# MK12_IO_Shield.net
KiCad netlist of a schematic drawn in EAGLE
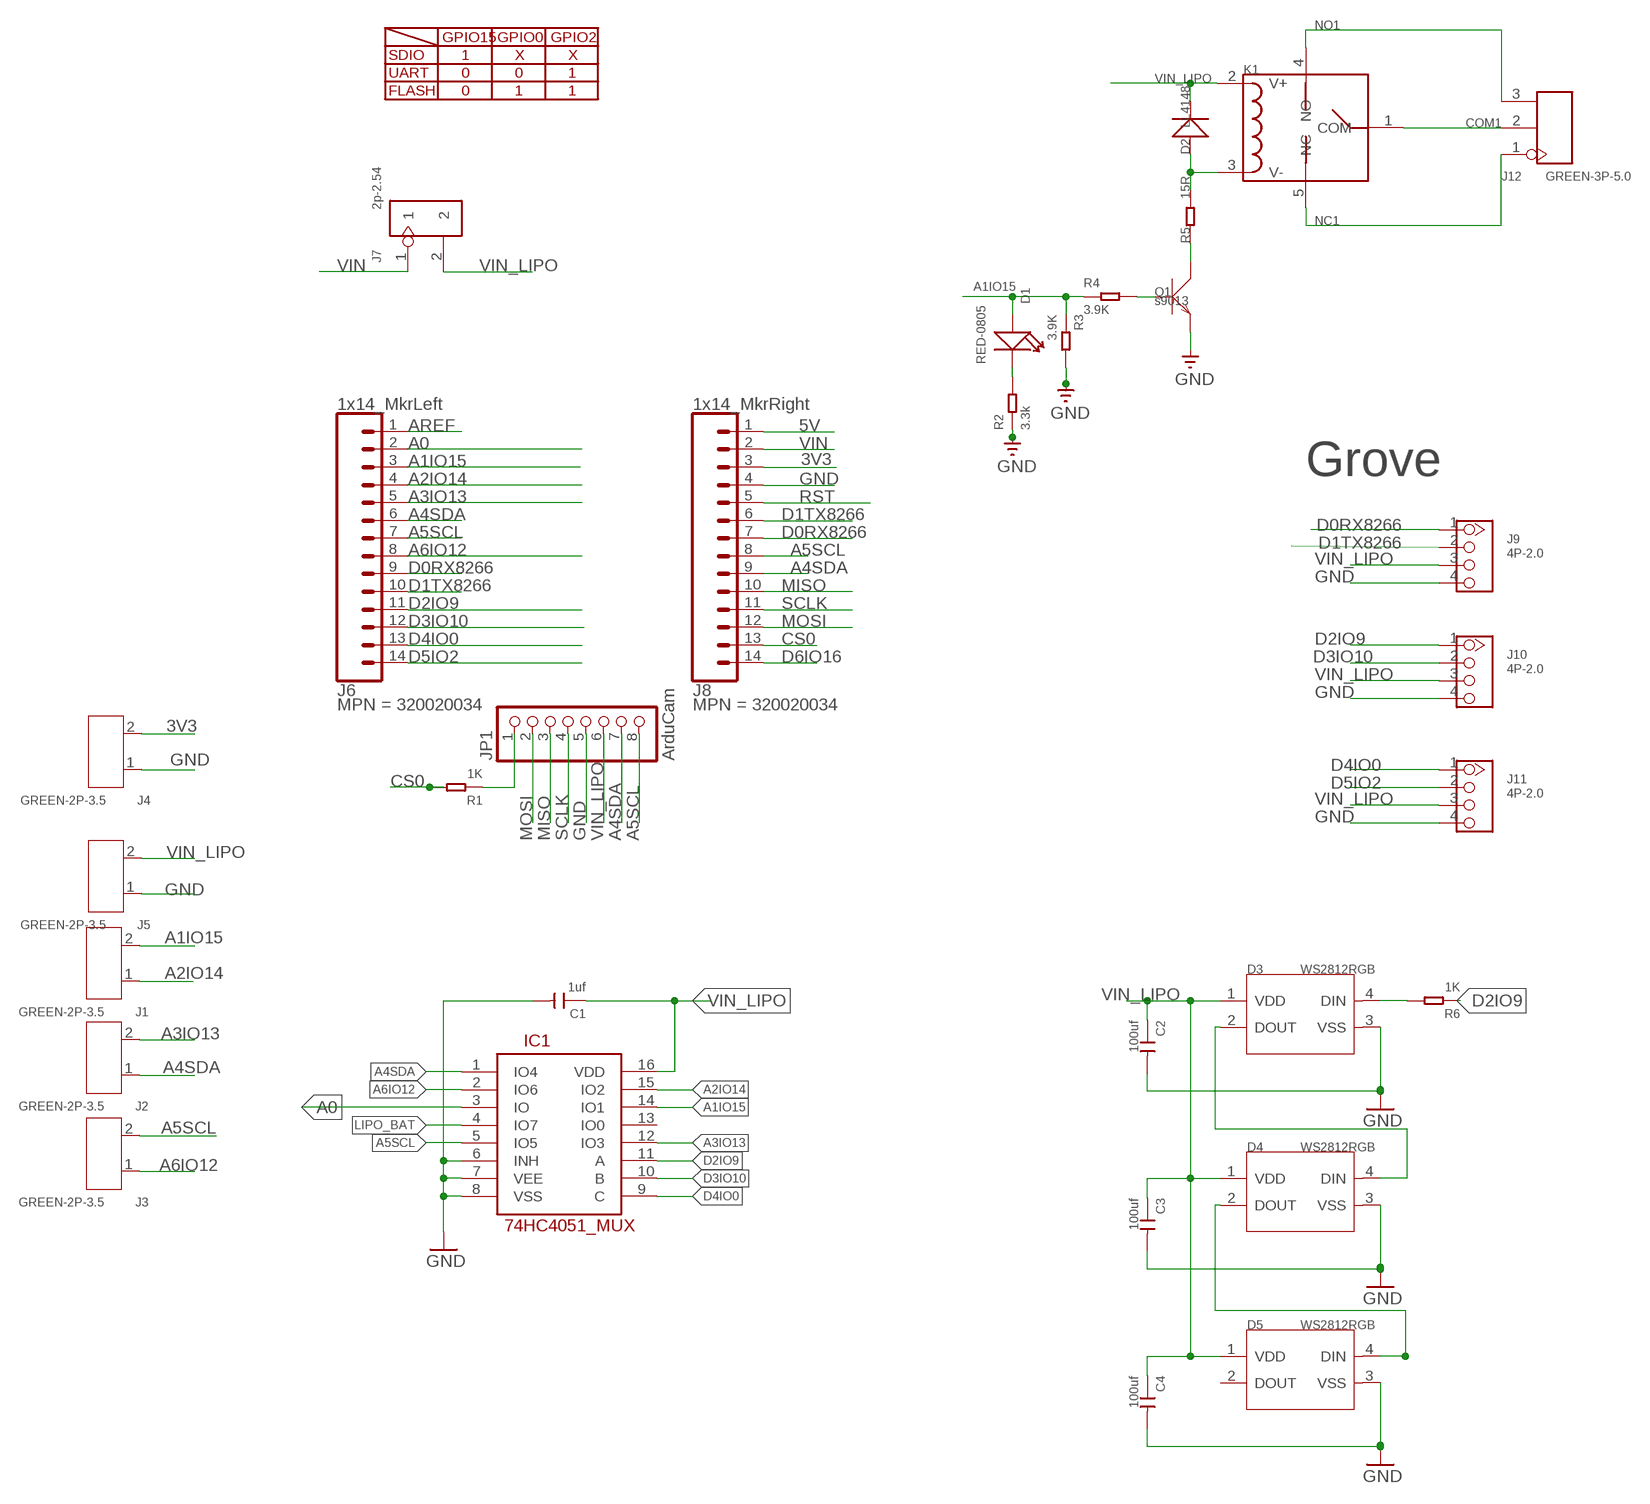
[diagram p0: schematic, sheet 1]

(export (version "E")
  (design (tool "Eeschema 10.0.6"))
  (components
    (comp (ref "C1")
      (value "1uf")
      (footprint "eagle-import:C0603")
      (fields (field (name "MPN") "CC0603KRX7R8BB105"))
      (libsource (lib "eagle-import") (part "CERAMIC-1UF-25V-10%-X7R(0603)"))
    )
    (comp (ref "C2")
      (value "100uf")
      (footprint "eagle-import:C1206")
      (fields (field (name "MPN") "GRM31CR60J107ME39L"))
      (libsource (lib "eagle-import") (part "CERAMIC-100UF-6.3V-20%-X5R(1206)"))
    )
    (comp (ref "C3")
      (value "100uf")
      (footprint "eagle-import:C1206")
      (fields (field (name "MPN") "GRM31CR60J107ME39L"))
      (libsource (lib "eagle-import") (part "CERAMIC-100UF-6.3V-20%-X5R(1206)"))
    )
    (comp (ref "C4")
      (value "100uf")
      (footprint "eagle-import:C1206")
      (fields (field (name "MPN") "GRM31CR60J107ME39L"))
      (libsource (lib "eagle-import") (part "CERAMIC-100UF-6.3V-20%-X5R(1206)"))
    )
    (comp (ref "D1")
      (value "RED-0805")
      (footprint "eagle-import:LED-0805")
      (fields (field (name "MPN") "17-215SURC/S530-A2/TR8"))
      (libsource (lib "eagle-import") (part "SMD-LED-CLEAR-RED(0805)"))
    )
    (comp (ref "D2")
      (value "LL4148")
      (footprint "eagle-import:LL-34")
      (libsource (lib "eagle-import") (part "D'1N4148-SMD'"))
    )
    (comp (ref "D3")
      (value "WS2812RGB")
      (footprint "eagle-import:LED4-SMD-5050")
      (libsource (lib "eagle-import") (part "SMD-RGB-LED-4P'WS2812B'"))
    )
    (comp (ref "D4")
      (value "WS2812RGB")
      (footprint "eagle-import:LED4-SMD-5050")
      (libsource (lib "eagle-import") (part "SMD-RGB-LED-4P'WS2812B'"))
    )
    (comp (ref "D5")
      (value "WS2812RGB")
      (footprint "eagle-import:LED4-SMD-5050")
      (libsource (lib "eagle-import") (part "SMD-RGB-LED-4P'WS2812B'"))
    )
    (comp (ref "IC1")
      (value "74HC4051_MUX")
      (footprint "eagle-import:SPARKFUN_SO16")
      (libsource (lib "eagle-import") (part "SPARKFUN_74HC4051_MUX"))
    )
    (comp (ref "J1")
      (value "GREEN-2P-3.5")
      (footprint "eagle-import:H2-3.5-7.0X7.0MM")
      (libsource (lib "eagle-import") (part "SCREW-TERMINAL-GREEN(2P-3.5)"))
    )
    (comp (ref "J2")
      (value "GREEN-2P-3.5")
      (footprint "eagle-import:H2-3.5-7.0X7.0MM")
      (libsource (lib "eagle-import") (part "SCREW-TERMINAL-GREEN(2P-3.5)"))
    )
    (comp (ref "J3")
      (value "GREEN-2P-3.5")
      (footprint "eagle-import:H2-3.5-7.0X7.0MM")
      (libsource (lib "eagle-import") (part "SCREW-TERMINAL-GREEN(2P-3.5)"))
    )
    (comp (ref "J4")
      (value "GREEN-2P-3.5")
      (footprint "eagle-import:H2-3.5-7.0X7.0MM")
      (libsource (lib "eagle-import") (part "SCREW-TERMINAL-GREEN(2P-3.5)"))
    )
    (comp (ref "J5")
      (value "GREEN-2P-3.5")
      (footprint "eagle-import:H2-3.5-7.0X7.0MM")
      (libsource (lib "eagle-import") (part "SCREW-TERMINAL-GREEN(2P-3.5)"))
    )
    (comp (ref "J6")
      (value "1x14_MkrLeft")
      (footprint "eagle-import:1X14_LOCK")
      (fields (field (name "MPN") "320020034"))
      (libsource (lib "eagle-import") (part "CONN_14LOCK"))
    )
    (comp (ref "J7")
      (value "2p-2.54")
      (footprint "eagle-import:H2-2.54")
      (fields (field (name "MPN") "P125-1102A0BS116A1"))
      (libsource (lib "eagle-import") (part "DIP-BLACK-MALE-HEADER-VERT(2P-2.54)"))
    )
    (comp (ref "J8")
      (value "1x14_MkrRight")
      (footprint "eagle-import:1X14_LOCK")
      (fields (field (name "MPN") "320020034"))
      (libsource (lib "eagle-import") (part "CONN_14LOCK"))
    )
    (comp (ref "J9")
      (value "4P-2.0")
      (footprint "eagle-import:HW4-2.0")
      (libsource (lib "eagle-import") (part "GROVE-CONNECTOR-DIP(4P-2.0)"))
    )
    (comp (ref "J10")
      (value "4P-2.0")
      (footprint "eagle-import:HW4-2.0")
      (libsource (lib "eagle-import") (part "GROVE-CONNECTOR-DIP(4P-2.0)"))
    )
    (comp (ref "J11")
      (value "4P-2.0")
      (footprint "eagle-import:HW4-2.0")
      (libsource (lib "eagle-import") (part "GROVE-CONNECTOR-DIP(4P-2.0)"))
    )
    (comp (ref "J12")
      (value "GREEN-3P-5.0")
      (footprint "eagle-import:H3-5.0-15.5X8.0MM")
      (libsource (lib "eagle-import") (part "SCREW-TERMINAL-GREEN(3P-5.0)"))
    )
    (comp (ref "JP1")
      (value "ArduCam")
      (footprint "eagle-import:MILLER_1X08-LOCK")
      (libsource (lib "eagle-import") (part "MILLER_PINHD-1X8LOCK"))
    )
    (comp (ref "K1")
      (value "RELAY-HLS8L-DC5V-S-CHLS8L-DC5V-S-C")
      (footprint "eagle-import:REY5-19.0X15.0X15.0MM")
      (libsource (lib "eagle-import") (part "RELAY-HLS8L-DC5V-S-CHLS8L-DC5V-S-C"))
    )
    (comp (ref "Q1")
      (value "s9013")
      (footprint "eagle-import:SOT23")
      (libsource (lib "eagle-import") (part "TRANSISTOR-NPN-SOT23"))
    )
    (comp (ref "R1")
      (value "1K")
      (footprint "eagle-import:R0805")
      (fields (field (name "MPN") "RC0805JR-071KL"))
      (libsource (lib "eagle-import") (part "SMD-RES-1K-5%-1/8W(0805)"))
    )
    (comp (ref "R2")
      (value "3.3k")
      (footprint "eagle-import:R0603")
      (libsource (lib "eagle-import") (part "SMD-RES-3.3K-5%-1/10W(0603)"))
    )
    (comp (ref "R3")
      (value "3.9K")
      (footprint "eagle-import:R0603")
      (fields (field (name "MPN") "RC0603JR-073K9L"))
      (libsource (lib "eagle-import") (part "SMD-RES-3.9K-5%-1/10W(0603)"))
    )
    (comp (ref "R4")
      (value "3.9K")
      (footprint "eagle-import:R0603")
      (fields (field (name "MPN") "RC0603JR-073K9L"))
      (libsource (lib "eagle-import") (part "SMD-RES-3.9K-5%-1/10W(0603)"))
    )
    (comp (ref "R5")
      (value "15R")
      (footprint "eagle-import:R0603")
      (libsource (lib "eagle-import") (part "R-0603"))
    )
    (comp (ref "R6")
      (value "1K")
      (footprint "eagle-import:R0805")
      (fields (field (name "MPN") "RC0805JR-071KL"))
      (libsource (lib "eagle-import") (part "SMD-RES-1K-5%-1/8W(0805)"))
    )
  )
  (nets
    (net (code "1") (name "/3V3") (class "Default")
      (node (ref "J4") (pin "2") (pinfunction "2_2") (pintype "bidirectional"))
      (node (ref "J8") (pin "3") (pinfunction "3_3") (pintype "passive"))
    )
    (net (code "2") (name "/5V") (class "Default")
      (node (ref "J8") (pin "1") (pinfunction "1_1") (pintype "passive"))
    )
    (net (code "3") (name "/AREF") (class "Default")
      (node (ref "J6") (pin "1") (pinfunction "1_1") (pintype "passive"))
    )
    (net (code "4") (name "/COM1") (class "Default")
      (node (ref "J12") (pin "2") (pinfunction "P$2_2") (pintype "bidirectional"))
      (node (ref "K1") (pin "1") (pinfunction "COM_1") (pintype "bidirectional"))
    )
    (net (code "5") (name "/CS0") (class "Default")
      (node (ref "J8") (pin "13") (pinfunction "13_13") (pintype "passive"))
      (node (ref "R1") (pin "2") (pinfunction "2_2") (pintype "passive"))
    )
    (net (code "6") (name "/D0RX8266") (class "Default")
      (node (ref "J6") (pin "9") (pinfunction "9_9") (pintype "passive"))
      (node (ref "J8") (pin "7") (pinfunction "7_7") (pintype "passive"))
      (node (ref "J9") (pin "1") (pinfunction "1_1") (pintype "bidirectional"))
    )
    (net (code "7") (name "/D1TX8266") (class "Default")
      (node (ref "J6") (pin "10") (pinfunction "10_10") (pintype "passive"))
      (node (ref "J8") (pin "6") (pinfunction "6_6") (pintype "passive"))
      (node (ref "J9") (pin "2") (pinfunction "2_2") (pintype "bidirectional"))
    )
    (net (code "8") (name "/D5IO2") (class "Default")
      (node (ref "J11") (pin "2") (pinfunction "2_2") (pintype "bidirectional"))
      (node (ref "J6") (pin "14") (pinfunction "14_14") (pintype "passive"))
    )
    (net (code "9") (name "/D6IO16") (class "Default")
      (node (ref "J8") (pin "14") (pinfunction "14_14") (pintype "passive"))
    )
    (net (code "10") (name "/MISO") (class "Default")
      (node (ref "J8") (pin "10") (pinfunction "10_10") (pintype "passive"))
      (node (ref "JP1") (pin "3") (pinfunction "3_3") (pintype "passive"))
    )
    (net (code "11") (name "/MOSI") (class "Default")
      (node (ref "J8") (pin "12") (pinfunction "12_12") (pintype "passive"))
      (node (ref "JP1") (pin "2") (pinfunction "2_2") (pintype "passive"))
    )
    (net (code "12") (name "/NC1") (class "Default")
      (node (ref "J12") (pin "1") (pinfunction "P$1_1") (pintype "bidirectional"))
      (node (ref "K1") (pin "5") (pinfunction "NC_5") (pintype "bidirectional"))
    )
    (net (code "13") (name "/NO1") (class "Default")
      (node (ref "J12") (pin "3") (pinfunction "P$3_3") (pintype "bidirectional"))
      (node (ref "K1") (pin "4") (pinfunction "NO_4") (pintype "bidirectional"))
    )
    (net (code "14") (name "/RST") (class "Default")
      (node (ref "J8") (pin "5") (pinfunction "5_5") (pintype "passive"))
    )
    (net (code "15") (name "/SCLK") (class "Default")
      (node (ref "J8") (pin "11") (pinfunction "11_11") (pintype "passive"))
      (node (ref "JP1") (pin "4") (pinfunction "4_4") (pintype "passive"))
    )
    (net (code "16") (name "/VIN") (class "Default")
      (node (ref "J7") (pin "1") (pinfunction "1_1") (pintype "bidirectional"))
      (node (ref "J8") (pin "2") (pinfunction "2_2") (pintype "passive"))
    )
    (net (code "17") (name "A0") (class "Default")
      (node (ref "IC1") (pin "3") (pinfunction "IO_3") (pintype "bidirectional"))
      (node (ref "J6") (pin "2") (pinfunction "2_2") (pintype "passive"))
    )
    (net (code "18") (name "A1IO15") (class "Default")
      (node (ref "D1") (pin "+") (pinfunction "+_+") (pintype "passive"))
      (node (ref "IC1") (pin "14") (pinfunction "IO1_14") (pintype "bidirectional"))
      (node (ref "J1") (pin "2") (pinfunction "2_2") (pintype "bidirectional"))
      (node (ref "J6") (pin "3") (pinfunction "3_3") (pintype "passive"))
      (node (ref "R3") (pin "1") (pinfunction "1_1") (pintype "passive"))
      (node (ref "R4") (pin "1") (pinfunction "1_1") (pintype "passive"))
    )
    (net (code "19") (name "A2IO14") (class "Default")
      (node (ref "IC1") (pin "15") (pinfunction "IO2_15") (pintype "bidirectional"))
      (node (ref "J1") (pin "1") (pinfunction "1_1") (pintype "bidirectional"))
      (node (ref "J6") (pin "4") (pinfunction "4_4") (pintype "passive"))
    )
    (net (code "20") (name "A3IO13") (class "Default")
      (node (ref "IC1") (pin "12") (pinfunction "IO3_12") (pintype "bidirectional"))
      (node (ref "J2") (pin "2") (pinfunction "2_2") (pintype "bidirectional"))
      (node (ref "J6") (pin "5") (pinfunction "5_5") (pintype "passive"))
    )
    (net (code "21") (name "A4SDA") (class "Default")
      (node (ref "IC1") (pin "1") (pinfunction "IO4_1") (pintype "bidirectional"))
      (node (ref "J2") (pin "1") (pinfunction "1_1") (pintype "bidirectional"))
      (node (ref "J6") (pin "6") (pinfunction "6_6") (pintype "passive"))
      (node (ref "J8") (pin "9") (pinfunction "9_9") (pintype "passive"))
      (node (ref "JP1") (pin "7") (pinfunction "7_7") (pintype "passive"))
    )
    (net (code "22") (name "A5SCL") (class "Default")
      (node (ref "IC1") (pin "5") (pinfunction "IO5_5") (pintype "bidirectional"))
      (node (ref "J3") (pin "2") (pinfunction "2_2") (pintype "bidirectional"))
      (node (ref "J6") (pin "7") (pinfunction "7_7") (pintype "passive"))
      (node (ref "J8") (pin "8") (pinfunction "8_8") (pintype "passive"))
      (node (ref "JP1") (pin "8") (pinfunction "8_8") (pintype "passive"))
    )
    (net (code "23") (name "A6IO12") (class "Default")
      (node (ref "IC1") (pin "2") (pinfunction "IO6_2") (pintype "bidirectional"))
      (node (ref "J3") (pin "1") (pinfunction "1_1") (pintype "bidirectional"))
      (node (ref "J6") (pin "8") (pinfunction "8_8") (pintype "passive"))
    )
    (net (code "24") (name "D2IO9") (class "Default")
      (node (ref "IC1") (pin "11") (pinfunction "A_11") (pintype "bidirectional"))
      (node (ref "J10") (pin "1") (pinfunction "1_1") (pintype "bidirectional"))
      (node (ref "J6") (pin "11") (pinfunction "11_11") (pintype "passive"))
      (node (ref "R6") (pin "1") (pinfunction "1_1") (pintype "passive"))
    )
    (net (code "25") (name "D3IO10") (class "Default")
      (node (ref "IC1") (pin "10") (pinfunction "B_10") (pintype "bidirectional"))
      (node (ref "J10") (pin "2") (pinfunction "2_2") (pintype "bidirectional"))
      (node (ref "J6") (pin "12") (pinfunction "12_12") (pintype "passive"))
    )
    (net (code "26") (name "D4IO0") (class "Default")
      (node (ref "IC1") (pin "9") (pinfunction "C_9") (pintype "bidirectional"))
      (node (ref "J11") (pin "1") (pinfunction "1_1") (pintype "bidirectional"))
      (node (ref "J6") (pin "13") (pinfunction "13_13") (pintype "passive"))
    )
    (net (code "27") (name "GND") (class "Default")
      (node (ref "C1") (pin "2") (pinfunction "2_2") (pintype "passive"))
      (node (ref "C2") (pin "2") (pinfunction "2_2") (pintype "passive"))
      (node (ref "C3") (pin "2") (pinfunction "2_2") (pintype "passive"))
      (node (ref "C4") (pin "2") (pinfunction "2_2") (pintype "passive"))
      (node (ref "D3") (pin "3") (pinfunction "VSS_3") (pintype "bidirectional"))
      (node (ref "D4") (pin "3") (pinfunction "VSS_3") (pintype "bidirectional"))
      (node (ref "D5") (pin "3") (pinfunction "VSS_3") (pintype "bidirectional"))
      (node (ref "IC1") (pin "6") (pinfunction "INH_6") (pintype "bidirectional"))
      (node (ref "IC1") (pin "7") (pinfunction "VEE_7") (pintype "bidirectional"))
      (node (ref "IC1") (pin "8") (pinfunction "VSS_8") (pintype "bidirectional"))
      (node (ref "J10") (pin "4") (pinfunction "4_4") (pintype "bidirectional"))
      (node (ref "J11") (pin "4") (pinfunction "4_4") (pintype "bidirectional"))
      (node (ref "J4") (pin "1") (pinfunction "1_1") (pintype "bidirectional"))
      (node (ref "J5") (pin "1") (pinfunction "1_1") (pintype "bidirectional"))
      (node (ref "J8") (pin "4") (pinfunction "4_4") (pintype "passive"))
      (node (ref "J9") (pin "4") (pinfunction "4_4") (pintype "bidirectional"))
      (node (ref "JP1") (pin "5") (pinfunction "5_5") (pintype "passive"))
      (node (ref "Q1") (pin "2") (pinfunction "E_2") (pintype "passive"))
      (node (ref "R2") (pin "1") (pinfunction "1_1") (pintype "passive"))
      (node (ref "R3") (pin "2") (pinfunction "2_2") (pintype "passive"))
    )
    (net (code "28") (name "LIPO_BAT") (class "Default")
      (node (ref "IC1") (pin "4") (pinfunction "IO7_4") (pintype "bidirectional"))
    )
    (net (code "29") (name "Net-(D1-Pad-)") (class "Default")
      (node (ref "D1") (pin "-") (pinfunction "-_-") (pintype "passive"))
      (node (ref "R2") (pin "2") (pinfunction "2_2") (pintype "passive"))
    )
    (net (code "30") (name "Net-(D2-+)") (class "Default")
      (node (ref "D2") (pin "A") (pinfunction "+_A") (pintype "passive"))
      (node (ref "K1") (pin "3") (pinfunction "V-_3") (pintype "bidirectional"))
      (node (ref "R5") (pin "2") (pinfunction "2_2") (pintype "passive"))
    )
    (net (code "31") (name "Net-(D3-DIN)") (class "Default")
      (node (ref "D3") (pin "4") (pinfunction "DIN_4") (pintype "bidirectional"))
      (node (ref "R6") (pin "2") (pinfunction "2_2") (pintype "passive"))
    )
    (net (code "32") (name "Net-(D3-DOUT)") (class "Default")
      (node (ref "D3") (pin "2") (pinfunction "DOUT_2") (pintype "bidirectional"))
      (node (ref "D4") (pin "4") (pinfunction "DIN_4") (pintype "bidirectional"))
    )
    (net (code "33") (name "Net-(D4-DOUT)") (class "Default")
      (node (ref "D4") (pin "2") (pinfunction "DOUT_2") (pintype "bidirectional"))
      (node (ref "D5") (pin "4") (pinfunction "DIN_4") (pintype "bidirectional"))
    )
    (net (code "34") (name "Net-(JP1-Pad1)") (class "Default")
      (node (ref "JP1") (pin "1") (pinfunction "1_1") (pintype "passive"))
      (node (ref "R1") (pin "1") (pinfunction "1_1") (pintype "passive"))
    )
    (net (code "35") (name "Net-(Q1-B)") (class "Default")
      (node (ref "Q1") (pin "1") (pinfunction "B_1") (pintype "passive"))
      (node (ref "R4") (pin "2") (pinfunction "2_2") (pintype "passive"))
    )
    (net (code "36") (name "Net-(Q1-C)") (class "Default")
      (node (ref "Q1") (pin "3") (pinfunction "C_3") (pintype "passive"))
      (node (ref "R5") (pin "1") (pinfunction "1_1") (pintype "passive"))
    )
    (net (code "37") (name "VIN_LIPO") (class "Default")
      (node (ref "C1") (pin "1") (pinfunction "1_1") (pintype "passive"))
      (node (ref "C2") (pin "1") (pinfunction "1_1") (pintype "passive"))
      (node (ref "C3") (pin "1") (pinfunction "1_1") (pintype "passive"))
      (node (ref "C4") (pin "1") (pinfunction "1_1") (pintype "passive"))
      (node (ref "D2") (pin "C") (pinfunction "-_C") (pintype "passive"))
      (node (ref "D3") (pin "1") (pinfunction "VDD_1") (pintype "bidirectional"))
      (node (ref "D4") (pin "1") (pinfunction "VDD_1") (pintype "bidirectional"))
      (node (ref "D5") (pin "1") (pinfunction "VDD_1") (pintype "bidirectional"))
      (node (ref "IC1") (pin "16") (pinfunction "VDD_16") (pintype "bidirectional"))
      (node (ref "J10") (pin "3") (pinfunction "3_3") (pintype "bidirectional"))
      (node (ref "J11") (pin "3") (pinfunction "3_3") (pintype "bidirectional"))
      (node (ref "J5") (pin "2") (pinfunction "2_2") (pintype "bidirectional"))
      (node (ref "J7") (pin "2") (pinfunction "2_2") (pintype "bidirectional"))
      (node (ref "J9") (pin "3") (pinfunction "3_3") (pintype "bidirectional"))
      (node (ref "JP1") (pin "6") (pinfunction "6_6") (pintype "passive"))
      (node (ref "K1") (pin "2") (pinfunction "V+_2") (pintype "bidirectional"))
    )
    (net (code "38") (name "unconnected-(D5-DOUT-Pad2)") (class "Default")
      (node (ref "D5") (pin "2") (pinfunction "DOUT_2") (pintype "bidirectional"))
    )
    (net (code "39") (name "unconnected-(IC1-IO0-Pad13)") (class "Default")
      (node (ref "IC1") (pin "13") (pinfunction "IO0_13") (pintype "bidirectional"))
    )
  )
)
